# TRIGGER.net
KiCad netlist of a schematic drawn in Altium Designer
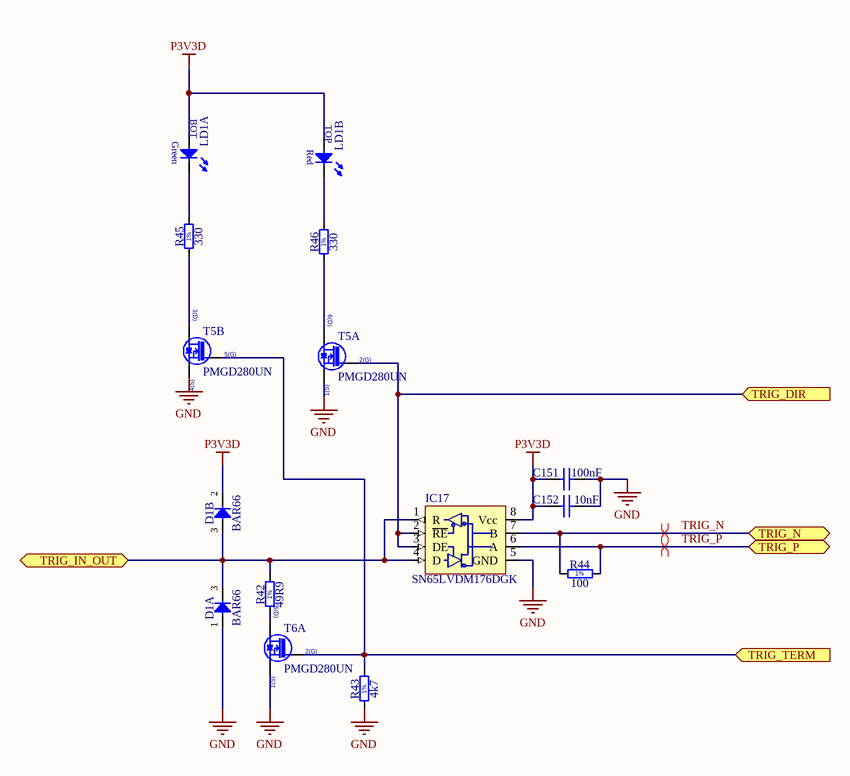
[diagram p0: TRIGGER.SchDoc]

(export (version "E")
  (design (tool "Eeschema 10.0.6"))
  (components
    (comp (ref "C151")
      (value "100nF")
      (footprint "CAPC0603X33N")
      (description "Non-polarised capacitor")
      (fields
        (field (name "PART NUMBER") "CC0201_100NF_6.3V_10%_X5R")
        (field (name "VOLTAGE") "6.3V")
        (field (name "AUTHOR") "CERN DEM JLC")
      )
      (libsource (lib "Capacitors") (part "Capacitor - non polarized"))
    )
    (comp (ref "C152")
      (value "10nF")
      (footprint "CAPC0603X33N")
      (description "Non-polarised capacitor")
      (fields
        (field (name "PART NUMBER") "CC0201_10NF_10V_10%_X5R")
        (field (name "VOLTAGE") "10V")
        (field (name "AUTHOR") "CERN DEM JLC")
      )
      (libsource (lib "Capacitors") (part "Capacitor - non polarized"))
    )
    (comp (ref "D1")
      (value "BAR66")
      (footprint "SOT95P240X110-3N")
      (description "Serial Diode")
      (fields
        (field (name "VOLTAGE") "150V")
        (field (name "POWER") "250mA")
        (field (name "AUTHOR") "CERN DEM JLC")
      )
      (libsource (lib "ICs And Semiconductors") (part "Diode x2 A1C3_A3C2"))
    )
    (comp (ref "IC17")
      (value "SN65LVDM176DGK")
      (footprint "MSOP8 TI/AD")
      (description "High Speed Differential Transceiver LVDS/LVTTL")
      (fields (field (name "MANUFACTURER") "Texas Instruments"))
      (libsource (lib "FMC_ADC") (part "SN65LVDM176"))
    )
    (comp (ref "LD1")
      (value "~")
      (footprint "553-xxxx-300")
      (description "LED x2 Red/Green 553-0711-300")
      (fields
        (field (name "MANUFACTURER PART NUMBER") "553-0711-300")
        (field (name "MANUFACTURER") "Dialight")
      )
      (libsource (lib "FMC_ADC") (part "LED x2 Red/Green 553-0711-300"))
    )
    (comp (ref "R42")
      (value "49R9")
      (footprint "RESC3225X70N")
      (description "Resistor - 1%")
      (fields
        (field (name "PART NUMBER") "R1210_49R9_1%_0.5W_100PPM_VISHAY_CRCW")
        (field (name "POWER") "0.5W")
        (field (name "AUTHOR") "CERN DEM JMW")
      )
      (libsource (lib "Resistors") (part "Resistor - 1%"))
    )
    (comp (ref "R43")
      (value "4k7")
      (footprint "RESC1005X40N")
      (description "Resistor - 1%")
      (fields
        (field (name "PART NUMBER") "R0402_4K7_1%_0.0625W_100PPM")
        (field (name "POWER") "0.0625W")
        (field (name "AUTHOR") "CERN DEM JLC")
      )
      (libsource (lib "Resistors") (part "Resistor - 1%"))
    )
    (comp (ref "R44")
      (value "100")
      (footprint "RESC1005X40N")
      (description "Resistor - 1%")
      (fields
        (field (name "PART NUMBER") "R0402_100R_1%_0.0625W_100PPM")
        (field (name "POWER") "0.0625W")
        (field (name "AUTHOR") "CERN DEM JLC")
      )
      (libsource (lib "Resistors") (part "Resistor - 1%"))
    )
    (comp (ref "R45")
      (value "330")
      (footprint "RESC1005X40N")
      (description "Resistor - 1%")
      (fields
        (field (name "PART NUMBER") "R0402_330R_1%_0.0625W_100PPM")
        (field (name "POWER") "0.0625W")
        (field (name "AUTHOR") "CERN DEM JLC")
      )
      (libsource (lib "Resistors") (part "Resistor - 1%"))
    )
    (comp (ref "R46")
      (value "330")
      (footprint "RESC1005X40N")
      (description "Resistor - 1%")
      (fields
        (field (name "PART NUMBER") "R0402_330R_1%_0.0625W_100PPM")
        (field (name "POWER") "0.0625W")
        (field (name "AUTHOR") "CERN DEM JLC")
      )
      (libsource (lib "Resistors") (part "Resistor - 1%"))
    )
    (comp (ref "T5")
      (value "PMGD280UN")
      (footprint "SOT65P210X110-6N")
      (description "Dual N-Channel micro TrenchMOS™ Ultra Low Level FET")
      (fields (field (name "MANUFACTURER") "NXP SEMICONDUCTORS") (field (name "AUTHOR") "CERN DEM JLC"))
      (libsource (lib "") (part "PMGD280UN_1"))
    )
    (comp (ref "T6")
      (value "PMGD280UN")
      (footprint "SOT65P210X110-6N")
      (description "Dual N-Channel micro TrenchMOS™ Ultra Low Level FET")
      (fields (field (name "MANUFACTURER") "NXP SEMICONDUCTORS") (field (name "AUTHOR") "CERN DEM JLC"))
      (libsource (lib "ICs And Semiconductors") (part "PMGD280UN"))
    )
  )
  (nets
    (net (code "1") (name "/TRIG_DIR") (class "Default")
      (node (ref "IC17") (pin "2") (pinfunction "~{RE}_2") (pintype "input"))
      (node (ref "IC17") (pin "3") (pinfunction "DE_3") (pintype "input"))
      (node (ref "T5") (pin "2") (pinfunction "G_2") (pintype "passive"))
    )
    (net (code "2") (name "/TRIG_IN_OUT") (class "Default")
      (node (ref "D1") (pin "3") (pinfunction "COMAC_3") (pintype "passive"))
      (node (ref "IC17") (pin "1") (pinfunction "R_1") (pintype "output"))
      (node (ref "IC17") (pin "4") (pinfunction "D_4") (pintype "input"))
      (node (ref "R42") (pin "2") (pinfunction "2_2") (pintype "passive"))
    )
    (net (code "3") (name "/TRIG_N") (class "Default")
      (node (ref "IC17") (pin "7") (pinfunction "B_7") (pintype "bidirectional"))
      (node (ref "R44") (pin "1") (pinfunction "1_1") (pintype "passive"))
    )
    (net (code "4") (name "/TRIG_P") (class "Default")
      (node (ref "IC17") (pin "6") (pinfunction "A_6") (pintype "bidirectional"))
      (node (ref "R44") (pin "2") (pinfunction "2_2") (pintype "passive"))
    )
    (net (code "5") (name "/TRIG_TERM") (class "Default")
      (node (ref "R43") (pin "2") (pinfunction "2_2") (pintype "passive"))
      (node (ref "T5") (pin "5") (pinfunction "G_5") (pintype "passive"))
      (node (ref "T6") (pin "2") (pinfunction "G_2") (pintype "passive"))
    )
    (net (code "6") (name "GND") (class "Default")
      (node (ref "C151") (pin "2") (pinfunction "2_2") (pintype "passive"))
      (node (ref "C152") (pin "2") (pinfunction "2_2") (pintype "passive"))
      (node (ref "D1") (pin "1") (pinfunction "A_1") (pintype "passive"))
      (node (ref "IC17") (pin "5") (pinfunction "GND_5") (pintype "power_in"))
      (node (ref "R43") (pin "1") (pinfunction "1_1") (pintype "passive"))
      (node (ref "T5") (pin "1") (pinfunction "S_1") (pintype "passive"))
      (node (ref "T5") (pin "4") (pinfunction "S_4") (pintype "passive"))
      (node (ref "T6") (pin "1") (pinfunction "S_1") (pintype "passive"))
    )
    (net (code "7") (name "Net-(LD1A-C)") (class "Default")
      (node (ref "LD1") (pin "1") (pinfunction "C_1") (pintype "passive"))
      (node (ref "R45") (pin "2") (pinfunction "2_2") (pintype "passive"))
    )
    (net (code "8") (name "Net-(LD1B-C)") (class "Default")
      (node (ref "LD1") (pin "3") (pinfunction "C_3") (pintype "passive"))
      (node (ref "R46") (pin "2") (pinfunction "2_2") (pintype "passive"))
    )
    (net (code "9") (name "Net-(T5A-D)") (class "Default")
      (node (ref "R46") (pin "1") (pinfunction "1_1") (pintype "passive"))
      (node (ref "T5") (pin "6") (pinfunction "D_6") (pintype "passive"))
    )
    (net (code "10") (name "Net-(T5B-D)") (class "Default")
      (node (ref "R45") (pin "1") (pinfunction "1_1") (pintype "passive"))
      (node (ref "T5") (pin "3") (pinfunction "D_3") (pintype "passive"))
    )
    (net (code "11") (name "Net-(T6A-D)") (class "Default")
      (node (ref "R42") (pin "1") (pinfunction "1_1") (pintype "passive"))
      (node (ref "T6") (pin "6") (pinfunction "D_6") (pintype "passive"))
    )
    (net (code "12") (name "P3V3D") (class "Default")
      (node (ref "C151") (pin "1") (pinfunction "1_1") (pintype "passive"))
      (node (ref "C152") (pin "1") (pinfunction "1_1") (pintype "passive"))
      (node (ref "D1") (pin "2") (pinfunction "C_2") (pintype "passive"))
      (node (ref "IC17") (pin "8") (pinfunction "Vcc_8") (pintype "power_in"))
      (node (ref "LD1") (pin "2") (pinfunction "A_2") (pintype "passive"))
      (node (ref "LD1") (pin "4") (pinfunction "A_4") (pintype "passive"))
    )
  )
)
